# VREG_RT9166-25PVL_with_EN.net
KiCad netlist of a schematic drawn in Altium Designer
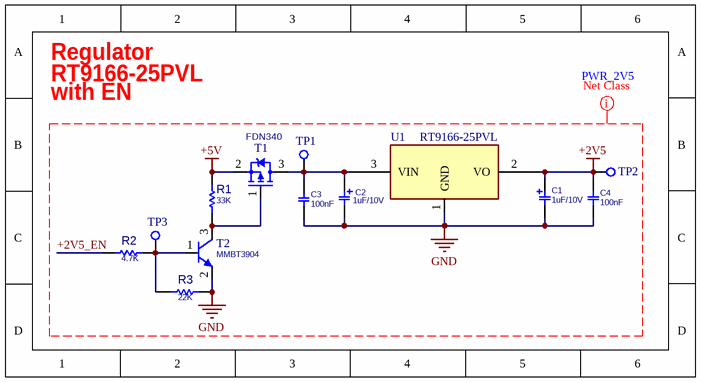
[diagram p0: VREG RT9166-25PVL with EN.SchDoc]

(export (version "E")
  (design (tool "Eeschema 10.0.6"))
  (components
    (comp (ref "C1")
      (value "1uF/10V")
      (footprint "C_TN_3216")
      (description "CAP, SMD, TAN")
      (libsource (lib "Passive") (part "CAP_SMD_TAN"))
    )
    (comp (ref "C2")
      (value "1uF/10V")
      (footprint "C_TN_3216")
      (description "CAP, SMD, TAN")
      (libsource (lib "Passive") (part "CAP_SMD_TAN"))
    )
    (comp (ref "C3")
      (value "100nF")
      (footprint "C0603S")
      (description "CAP, SMD, MLCC")
      (fields (field (name "MANF_P#") "MANF_PART#") (field (name "MANF") "Murata"))
      (libsource (lib "Passive") (part "CAP_SMD_MLCC"))
    )
    (comp (ref "C4")
      (value "100nF")
      (footprint "C0603S")
      (description "CAP, SMD, MLCC")
      (fields (field (name "MANF_P#") "MANF_PART#") (field (name "MANF") "Murata"))
      (libsource (lib "Passive") (part "CAP_SMD_MLCC"))
    )
    (comp (ref "R1")
      (value "33K")
      (footprint "R0603S")
      (description "RES, SMD")
      (fields (field (name "MANF_P#") "RK73H1ETTP4701F") (field (name "MANF") "KOA SPEER"))
      (libsource (lib "Passive") (part "RES_SMD"))
    )
    (comp (ref "R2")
      (value "4.7K")
      (footprint "R0603S")
      (description "RES, SMD")
      (fields (field (name "MANF_P#") "RK73H1ETTP4701F") (field (name "MANF") "KOA SPEER"))
      (libsource (lib "Passive") (part "RES_SMD"))
    )
    (comp (ref "R3")
      (value "22K")
      (footprint "R0603S")
      (description "RES, SMD")
      (fields (field (name "MANF_P#") "RK73H1ETTP4701F") (field (name "MANF") "KOA SPEER"))
      (libsource (lib "Passive") (part "RES_SMD"))
    )
    (comp (ref "T1")
      (value "FDN340")
      (footprint "SOT23_3")
      (description "MOSFET SMD P-CH 20V 2A")
      (fields (field (name "MANF_P#") "FDN360"))
      (libsource (lib "Transistor FET") (part "MOSP_FDN340_SOT23"))
    )
    (comp (ref "T2")
      (value "MMBT3904")
      (footprint "SOT23_3")
      (description "BJT, NPN, 40V, 0.2A, SMD, SOT23")
      (fields (field (name "MANF") "Diodes, NXP, FAIRCHILD, ON"))
      (libsource (lib "Transistor BJT") (part "NPN_MMBT3904_SOT23"))
    )
    (comp (ref "TP1")
      (value "Test Point")
      (footprint "TPSMD_C1")
      (libsource (lib "Passives") (part "Test Point"))
    )
    (comp (ref "TP2")
      (value "Test Point")
      (footprint "TPSMD_C1")
      (libsource (lib "Passives") (part "Test Point"))
    )
    (comp (ref "TP3")
      (value "Test Point")
      (footprint "TPSMD_C1")
      (libsource (lib "Passives") (part "Test Point"))
    )
    (comp (ref "U1")
      (value "RT9166-25PVL")
      (footprint "SOT23_3")
      (description "REG, Linear, Fixed, 2.5v, 0.3A/0.6A, SOT23")
      (fields (field (name "MANF") "TI"))
      (libsource (lib "PW Components 97_481") (part "VREG_RT9166A-25PVL_SOT23"))
    )
  )
  (nets
    (net (code "1") (name "+2V5") (class "Default")
      (node (ref "C1") (pin "1") (pinfunction "1_1") (pintype "passive"))
      (node (ref "C4") (pin "1") (pinfunction "1_1") (pintype "passive"))
      (node (ref "TP2") (pin "1") (pinfunction "TP_1") (pintype "passive"))
      (node (ref "U1") (pin "2") (pinfunction "VO_2") (pintype "passive"))
    )
    (net (code "2") (name "+5V") (class "Default")
      (node (ref "R1") (pin "2") (pinfunction "2_2") (pintype "passive"))
      (node (ref "T1") (pin "2") (pinfunction "S_2") (pintype "passive"))
    )
    (net (code "3") (name "/+2V5_EN") (class "Default")
      (node (ref "R2") (pin "2") (pinfunction "2_2") (pintype "passive"))
    )
    (net (code "4") (name "GND") (class "Default")
      (node (ref "C1") (pin "2") (pinfunction "2_2") (pintype "passive"))
      (node (ref "C2") (pin "2") (pinfunction "2_2") (pintype "passive"))
      (node (ref "C3") (pin "2") (pinfunction "2_2") (pintype "passive"))
      (node (ref "C4") (pin "2") (pinfunction "2_2") (pintype "passive"))
      (node (ref "R3") (pin "1") (pinfunction "1_1") (pintype "passive"))
      (node (ref "T2") (pin "2") (pinfunction "E_2") (pintype "passive"))
      (node (ref "U1") (pin "1") (pinfunction "GND_1") (pintype "passive"))
    )
    (net (code "5") (name "Net-(T1-D)") (class "Default")
      (node (ref "C2") (pin "1") (pinfunction "1_1") (pintype "passive"))
      (node (ref "C3") (pin "1") (pinfunction "1_1") (pintype "passive"))
      (node (ref "T1") (pin "3") (pinfunction "D_3") (pintype "passive"))
      (node (ref "TP1") (pin "1") (pinfunction "TP_1") (pintype "passive"))
      (node (ref "U1") (pin "3") (pinfunction "VIN_3") (pintype "passive"))
    )
    (net (code "6") (name "Net-(T1-G)") (class "Default")
      (node (ref "R1") (pin "1") (pinfunction "1_1") (pintype "passive"))
      (node (ref "T1") (pin "1") (pinfunction "G_1") (pintype "passive"))
      (node (ref "T2") (pin "3") (pinfunction "C_3") (pintype "passive"))
    )
    (net (code "7") (name "Net-(T2-B)") (class "Default")
      (node (ref "R2") (pin "1") (pinfunction "1_1") (pintype "passive"))
      (node (ref "R3") (pin "2") (pinfunction "2_2") (pintype "passive"))
      (node (ref "T2") (pin "1") (pinfunction "B_1") (pintype "passive"))
      (node (ref "TP3") (pin "1") (pinfunction "TP_1") (pintype "passive"))
    )
  )
)
